# dcmotorBAT_2.net
KiCad netlist of a schematic drawn in EAGLE
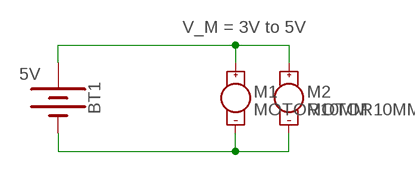
[diagram p0: schematic, sheet 1]

(export (version "E")
  (design (tool "Eeschema 10.0.6"))
  (components
    (comp (ref "BT1")
      (value "BATTERY-9V")
      (footprint "eagle-import:BATTCON_9V")
      (libsource (lib "eagle-import") (part "BATTERY-9V"))
    )
    (comp (ref "M1")
      (value "MOTOR10MM")
      (footprint "eagle-import:VIBE-MOTOR-10MM")
      (libsource (lib "eagle-import") (part "MOTOR10MM"))
    )
    (comp (ref "M2")
      (value "MOTOR10MM")
      (footprint "eagle-import:VIBE-MOTOR-10MM")
      (libsource (lib "eagle-import") (part "MOTOR10MM"))
    )
  )
  (nets
    (net (code "1") (name "Net-(BT1-Pad+)") (class "Default")
      (node (ref "BT1") (pin "+") (pinfunction "+_+") (pintype "power_in"))
      (node (ref "M1") (pin "+") (pinfunction "+_+") (pintype "bidirectional"))
      (node (ref "M2") (pin "+") (pinfunction "+_+") (pintype "bidirectional"))
    )
    (net (code "2") (name "Net-(BT1-Pad-)") (class "Default")
      (node (ref "BT1") (pin "-") (pinfunction "-_-") (pintype "power_in"))
      (node (ref "M1") (pin "-") (pinfunction "-_-") (pintype "bidirectional"))
      (node (ref "M2") (pin "-") (pinfunction "-_-") (pintype "bidirectional"))
    )
  )
)
